# backscatter_frontend.net
KiCad netlist of a schematic drawn in EAGLE
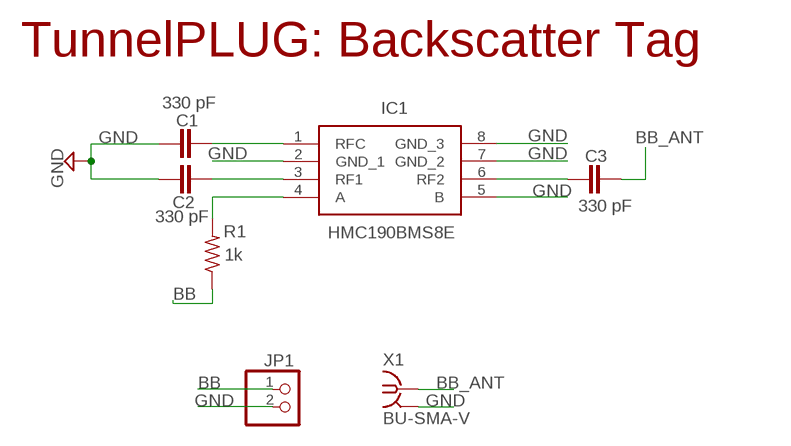
[diagram p0: schematic, sheet 1]

(export (version "E")
  (design (tool "Eeschema 10.0.6"))
  (components
    (comp (ref "C1")
      (value "330 pF")
      (footprint "eagle-import:C0603K")
      (libsource (lib "eagle-import") (part "C-EUC0603K"))
    )
    (comp (ref "C2")
      (value "330 pF")
      (footprint "eagle-import:C0603K")
      (libsource (lib "eagle-import") (part "C-EUC0603K"))
    )
    (comp (ref "C3")
      (value "330 pF")
      (footprint "eagle-import:C0603K")
      (libsource (lib "eagle-import") (part "C-EUC0603K"))
    )
    (comp (ref "IC1")
      (value "HMC190BMS8E")
      (footprint "eagle-import:SOP65P488X110-8N")
      (fields (field (name "MOUSER_PART_NUMBER") "584-HMC190BMS8E"))
      (libsource (lib "eagle-import") (part "HMC190BMS8E"))
    )
    (comp (ref "JP1")
      (value "PINHD-1X2/L90")
      (footprint "eagle-import:1X02_90")
      (libsource (lib "eagle-import") (part "PINHD-1X2/L90"))
    )
    (comp (ref "R1")
      (value "1k")
      (footprint "eagle-import:M0805")
      (libsource (lib "eagle-import") (part "R-US_M0805"))
    )
    (comp (ref "X1")
      (value "BU-SMA-V")
      (footprint "eagle-import:BU-SMA-V")
      (libsource (lib "eagle-import") (part "BU-SMA-V"))
    )
  )
  (nets
    (net (code "1") (name "/BB") (class "Default")
      (node (ref "JP1") (pin "1") (pinfunction "1_1") (pintype "passive"))
      (node (ref "R1") (pin "1") (pinfunction "1_1") (pintype "passive"))
    )
    (net (code "2") (name "/BB_ANT") (class "Default")
      (node (ref "C3") (pin "2") (pinfunction "2_2") (pintype "passive"))
      (node (ref "X1") (pin "1") (pinfunction "1_1") (pintype "passive"))
    )
    (net (code "3") (name "GND") (class "Default")
      (node (ref "C1") (pin "1") (pinfunction "1_1") (pintype "passive"))
      (node (ref "C2") (pin "1") (pinfunction "1_1") (pintype "passive"))
      (node (ref "IC1") (pin "2") (pinfunction "GND_1_2") (pintype "bidirectional"))
      (node (ref "IC1") (pin "5") (pinfunction "B_5") (pintype "bidirectional"))
      (node (ref "IC1") (pin "7") (pinfunction "GND_2_7") (pintype "bidirectional"))
      (node (ref "IC1") (pin "8") (pinfunction "GND_3_8") (pintype "bidirectional"))
      (node (ref "JP1") (pin "2") (pinfunction "2_2") (pintype "passive"))
      (node (ref "X1") (pin "2") (pinfunction "2_2") (pintype "passive"))
      (node (ref "X1") (pin "3") (pinfunction "2_3") (pintype "passive"))
      (node (ref "X1") (pin "4") (pinfunction "2_4") (pintype "passive"))
      (node (ref "X1") (pin "5") (pinfunction "2_5") (pintype "passive"))
    )
    (net (code "4") (name "Net-(IC1-A)") (class "Default")
      (node (ref "IC1") (pin "4") (pinfunction "A_4") (pintype "bidirectional"))
      (node (ref "R1") (pin "2") (pinfunction "2_2") (pintype "passive"))
    )
    (net (code "5") (name "Net-(IC1-RF1)") (class "Default")
      (node (ref "C2") (pin "2") (pinfunction "2_2") (pintype "passive"))
      (node (ref "IC1") (pin "3") (pinfunction "RF1_3") (pintype "bidirectional"))
    )
    (net (code "6") (name "Net-(IC1-RF2)") (class "Default")
      (node (ref "C3") (pin "1") (pinfunction "1_1") (pintype "passive"))
      (node (ref "IC1") (pin "6") (pinfunction "RF2_6") (pintype "bidirectional"))
    )
    (net (code "7") (name "Net-(IC1-RFC)") (class "Default")
      (node (ref "C1") (pin "2") (pinfunction "2_2") (pintype "passive"))
      (node (ref "IC1") (pin "1") (pinfunction "RFC_1") (pintype "bidirectional"))
    )
  )
)
